# jan_ray.net
KiCad netlist of a schematic drawn in EAGLE
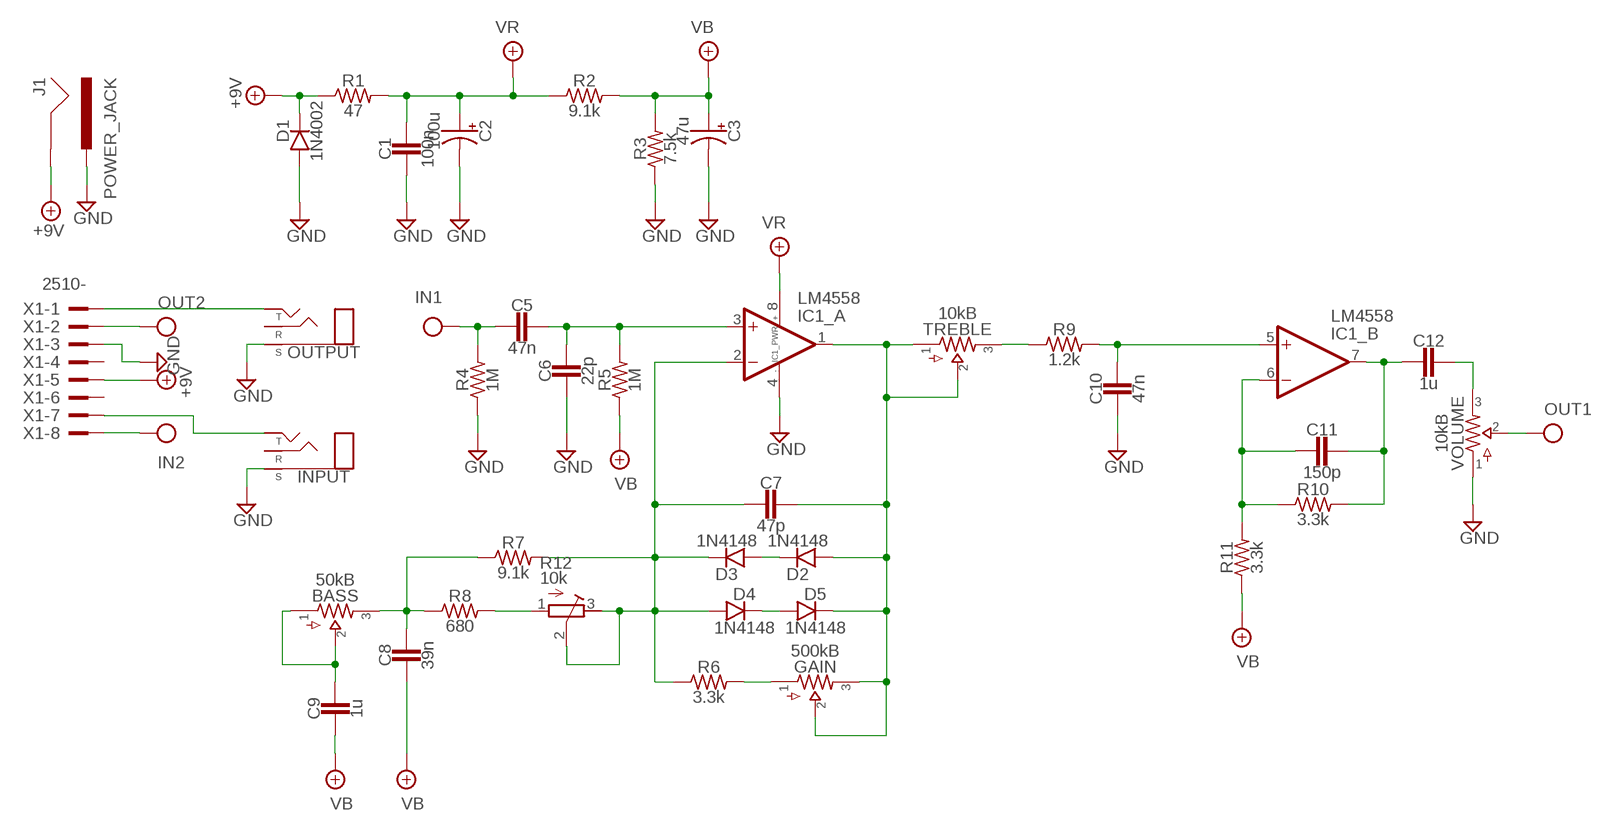
[diagram p0: schematic, sheet 1]

(export (version "E")
  (design (tool "Eeschema 10.0.6"))
  (components
    (comp (ref "BASS")
      (value "50kB")
      (footprint "eagle-import:16MM")
      (libsource (lib "eagle-import") (part "POTS16MM"))
    )
    (comp (ref "C1")
      (value "100n")
      (footprint "eagle-import:050X030_025_2")
      (libsource (lib "eagle-import") (part "CER/FILM2"))
    )
    (comp (ref "C2")
      (value "100u")
      (footprint "eagle-import:050_020")
      (libsource (lib "eagle-import") (part "0500"))
    )
    (comp (ref "C3")
      (value "47u")
      (footprint "eagle-import:050_020")
      (libsource (lib "eagle-import") (part "0500"))
    )
    (comp (ref "C5")
      (value "47n")
      (footprint "eagle-import:BOX_SMALL")
      (libsource (lib "eagle-import") (part "CER/FILMBOX.1"))
    )
    (comp (ref "C6")
      (value "22p")
      (footprint "eagle-import:050X030_025_2")
      (libsource (lib "eagle-import") (part "CER/FILM2"))
    )
    (comp (ref "C7")
      (value "47p")
      (footprint "eagle-import:050X030_025_2")
      (libsource (lib "eagle-import") (part "CER/FILM2"))
    )
    (comp (ref "C8")
      (value "39n")
      (footprint "eagle-import:BOX_SMALL")
      (libsource (lib "eagle-import") (part "CER/FILMBOX.1"))
    )
    (comp (ref "C9")
      (value "1u")
      (footprint "eagle-import:BOX_BIG")
      (libsource (lib "eagle-import") (part "CER/FILMBOX.3"))
    )
    (comp (ref "C10")
      (value "47n")
      (footprint "eagle-import:BOX_SMALL")
      (libsource (lib "eagle-import") (part "CER/FILMBOX.1"))
    )
    (comp (ref "C11")
      (value "150p")
      (footprint "eagle-import:050X030_025_2")
      (libsource (lib "eagle-import") (part "CER/FILM2"))
    )
    (comp (ref "C12")
      (value "1u")
      (footprint "eagle-import:BOX_BIG")
      (libsource (lib "eagle-import") (part "CER/FILMBOX.3"))
    )
    (comp (ref "D1")
      (value "1N4002")
      (footprint "eagle-import:DO41-2")
      (libsource (lib "eagle-import") (part "DO41.2"))
    )
    (comp (ref "D2")
      (value "1N4148")
      (footprint "eagle-import:DO35-2")
      (libsource (lib "eagle-import") (part "DO35.2"))
    )
    (comp (ref "D3")
      (value "1N4148")
      (footprint "eagle-import:DO35-2")
      (libsource (lib "eagle-import") (part "DO35.2"))
    )
    (comp (ref "D4")
      (value "1N4148")
      (footprint "eagle-import:DO35-2")
      (libsource (lib "eagle-import") (part "DO35.2"))
    )
    (comp (ref "D5")
      (value "1N4148")
      (footprint "eagle-import:DO35-2")
      (libsource (lib "eagle-import") (part "DO35.2"))
    )
    (comp (ref "GAIN")
      (value "500kB")
      (footprint "eagle-import:16MM")
      (libsource (lib "eagle-import") (part "POTS16MM"))
    )
    (comp (ref "IC1")
      (value "LM4558")
      (footprint "eagle-import:DIL08")
      (libsource (lib "eagle-import") (part "DUALTH"))
    )
    (comp (ref "INPUT")
      (value "STEREONMJ")
      (footprint "eagle-import:NMJ6HCD2")
      (libsource (lib "eagle-import") (part "STEREONMJ"))
    )
    (comp (ref "J1")
      (value "POWER_JACK")
      (footprint "eagle-import:POWER_JACK_PTH")
      (libsource (lib "eagle-import") (part "POWER_JACK"))
    )
    (comp (ref "OUTPUT")
      (value "STEREONMJ")
      (footprint "eagle-import:NMJ6HCD2")
      (libsource (lib "eagle-import") (part "STEREONMJ"))
    )
    (comp (ref "R1")
      (value "47")
      (footprint "eagle-import:R0207_3")
      (libsource (lib "eagle-import") (part "R_.3B"))
    )
    (comp (ref "R2")
      (value "9.1k")
      (footprint "eagle-import:R0207_3")
      (libsource (lib "eagle-import") (part "R_.3B"))
    )
    (comp (ref "R3")
      (value "7.5k")
      (footprint "eagle-import:R0207_3")
      (libsource (lib "eagle-import") (part "R_.3B"))
    )
    (comp (ref "R4")
      (value "1M")
      (footprint "eagle-import:R0207_3")
      (libsource (lib "eagle-import") (part "R_.3B"))
    )
    (comp (ref "R5")
      (value "1M")
      (footprint "eagle-import:R0207_3")
      (libsource (lib "eagle-import") (part "R_.3B"))
    )
    (comp (ref "R6")
      (value "3.3k")
      (footprint "eagle-import:R0207_3")
      (libsource (lib "eagle-import") (part "R_.3B"))
    )
    (comp (ref "R7")
      (value "9.1k")
      (footprint "eagle-import:R0207_3")
      (libsource (lib "eagle-import") (part "R_.3B"))
    )
    (comp (ref "R8")
      (value "680")
      (footprint "eagle-import:R0207_3")
      (libsource (lib "eagle-import") (part "R_.3B"))
    )
    (comp (ref "R9")
      (value "1.2k")
      (footprint "eagle-import:R0207_3")
      (libsource (lib "eagle-import") (part "R_.3B"))
    )
    (comp (ref "R10")
      (value "3.3k")
      (footprint "eagle-import:R0207_3")
      (libsource (lib "eagle-import") (part "R_.3B"))
    )
    (comp (ref "R11")
      (value "3.3k")
      (footprint "eagle-import:R0207_3")
      (libsource (lib "eagle-import") (part "R_.3B"))
    )
    (comp (ref "R12")
      (value "10k")
      (footprint "eagle-import:RTRIM3296W")
      (libsource (lib "eagle-import") (part "R-TRIMM3296W"))
    )
    (comp (ref "TREBLE")
      (value "10kB")
      (footprint "eagle-import:16MM")
      (libsource (lib "eagle-import") (part "POTS16MM"))
    )
    (comp (ref "VOLUME")
      (value "10kB")
      (footprint "eagle-import:16MM")
      (libsource (lib "eagle-import") (part "POTS16MM"))
    )
    (comp (ref "X1")
      (value "2510-")
      (footprint "eagle-import:PAK100_2500-10")
      (fields (field (name "MF") "3M") (field (name "MPN") "2510-6002UB"))
      (libsource (lib "eagle-import") (part "2510-"))
    )
  )
  (nets
    (net (code "1") (name "+9V") (class "Default")
      (node (ref "D1") (pin "C") (pinfunction "C_C") (pintype "passive"))
      (node (ref "J1") (pin "GND") (pinfunction "GND_GND") (pintype "bidirectional"))
      (node (ref "R1") (pin "1") (pinfunction "1_1") (pintype "passive"))
      (node (ref "X1") (pin "5") (pinfunction "KL_5") (pintype "passive"))
    )
    (net (code "2") (name "GND") (class "Default")
      (node (ref "C1") (pin "2") (pinfunction "2_2") (pintype "passive"))
      (node (ref "C10") (pin "2") (pinfunction "2_2") (pintype "passive"))
      (node (ref "C2") (pin "-") (pinfunction "-_-") (pintype "passive"))
      (node (ref "C3") (pin "-") (pinfunction "-_-") (pintype "passive"))
      (node (ref "C6") (pin "2") (pinfunction "2_2") (pintype "passive"))
      (node (ref "D1") (pin "A") (pinfunction "A_A") (pintype "passive"))
      (node (ref "IC1") (pin "4") (pinfunction "V-_4") (pintype "power_in"))
      (node (ref "INPUT") (pin "S") (pinfunction "S_S") (pintype "passive"))
      (node (ref "J1") (pin "PWR") (pinfunction "PWR_PWR") (pintype "bidirectional"))
      (node (ref "OUTPUT") (pin "S") (pinfunction "S_S") (pintype "passive"))
      (node (ref "R3") (pin "1") (pinfunction "1_1") (pintype "passive"))
      (node (ref "R4") (pin "1") (pinfunction "1_1") (pintype "passive"))
      (node (ref "VOLUME") (pin "1") (pinfunction "1_1") (pintype "passive"))
      (node (ref "X1") (pin "3") (pinfunction "KL_3") (pintype "passive"))
    )
    (net (code "3") (name "IN") (class "Default")
      (node (ref "C5") (pin "2") (pinfunction "2_2") (pintype "passive"))
      (node (ref "R4") (pin "2") (pinfunction "2_2") (pintype "passive"))
      (node (ref "X1") (pin "8") (pinfunction "KL_8") (pintype "passive"))
    )
    (net (code "4") (name "Net-(BASS-Pad1)") (class "Default")
      (node (ref "BASS") (pin "1") (pinfunction "1_1") (pintype "passive"))
      (node (ref "BASS") (pin "2") (pinfunction "2_2") (pintype "passive"))
      (node (ref "C9") (pin "1") (pinfunction "1_1") (pintype "passive"))
    )
    (net (code "5") (name "Net-(BASS-Pad3)") (class "Default")
      (node (ref "BASS") (pin "3") (pinfunction "3_3") (pintype "passive"))
      (node (ref "C8") (pin "1") (pinfunction "1_1") (pintype "passive"))
      (node (ref "R7") (pin "1") (pinfunction "1_1") (pintype "passive"))
      (node (ref "R8") (pin "1") (pinfunction "1_1") (pintype "passive"))
    )
    (net (code "6") (name "Net-(C12-Pad1)") (class "Default")
      (node (ref "C12") (pin "1") (pinfunction "1_1") (pintype "passive"))
      (node (ref "VOLUME") (pin "3") (pinfunction "3_3") (pintype "passive"))
    )
    (net (code "7") (name "Net-(D2-PadC)") (class "Default")
      (node (ref "D2") (pin "C") (pinfunction "C_C") (pintype "passive"))
      (node (ref "D3") (pin "A") (pinfunction "A_A") (pintype "passive"))
    )
    (net (code "8") (name "Net-(D4-PadC)") (class "Default")
      (node (ref "D4") (pin "C") (pinfunction "C_C") (pintype "passive"))
      (node (ref "D5") (pin "A") (pinfunction "A_A") (pintype "passive"))
    )
    (net (code "9") (name "Net-(GAIN-Pad1)") (class "Default")
      (node (ref "GAIN") (pin "1") (pinfunction "1_1") (pintype "passive"))
      (node (ref "R6") (pin "2") (pinfunction "2_2") (pintype "passive"))
    )
    (net (code "10") (name "Net-(IC1A-+IN)") (class "Default")
      (node (ref "C5") (pin "1") (pinfunction "1_1") (pintype "passive"))
      (node (ref "C6") (pin "1") (pinfunction "1_1") (pintype "passive"))
      (node (ref "IC1") (pin "3") (pinfunction "+IN_3") (pintype "input"))
      (node (ref "R5") (pin "2") (pinfunction "2_2") (pintype "passive"))
    )
    (net (code "11") (name "Net-(IC1A--IN)") (class "Default")
      (node (ref "C7") (pin "2") (pinfunction "2_2") (pintype "passive"))
      (node (ref "D3") (pin "C") (pinfunction "C_C") (pintype "passive"))
      (node (ref "D4") (pin "A") (pinfunction "A_A") (pintype "passive"))
      (node (ref "IC1") (pin "2") (pinfunction "-IN_2") (pintype "input"))
      (node (ref "R12") (pin "2") (pinfunction "S_2") (pintype "passive"))
      (node (ref "R12") (pin "3") (pinfunction "E_3") (pintype "passive"))
      (node (ref "R6") (pin "1") (pinfunction "1_1") (pintype "passive"))
      (node (ref "R7") (pin "2") (pinfunction "2_2") (pintype "passive"))
    )
    (net (code "12") (name "Net-(IC1A-OUT)") (class "Default")
      (node (ref "C7") (pin "1") (pinfunction "1_1") (pintype "passive"))
      (node (ref "D2") (pin "A") (pinfunction "A_A") (pintype "passive"))
      (node (ref "D5") (pin "C") (pinfunction "C_C") (pintype "passive"))
      (node (ref "GAIN") (pin "2") (pinfunction "2_2") (pintype "passive"))
      (node (ref "GAIN") (pin "3") (pinfunction "3_3") (pintype "passive"))
      (node (ref "IC1") (pin "1") (pinfunction "OUT_1") (pintype "output"))
      (node (ref "TREBLE") (pin "1") (pinfunction "1_1") (pintype "passive"))
      (node (ref "TREBLE") (pin "2") (pinfunction "2_2") (pintype "passive"))
    )
    (net (code "13") (name "Net-(IC1B-+IN)") (class "Default")
      (node (ref "C10") (pin "1") (pinfunction "1_1") (pintype "passive"))
      (node (ref "IC1") (pin "5") (pinfunction "+IN_5") (pintype "input"))
      (node (ref "R9") (pin "2") (pinfunction "2_2") (pintype "passive"))
    )
    (net (code "14") (name "Net-(IC1B--IN)") (class "Default")
      (node (ref "C11") (pin "2") (pinfunction "2_2") (pintype "passive"))
      (node (ref "IC1") (pin "6") (pinfunction "-IN_6") (pintype "input"))
      (node (ref "R10") (pin "1") (pinfunction "1_1") (pintype "passive"))
      (node (ref "R11") (pin "2") (pinfunction "2_2") (pintype "passive"))
    )
    (net (code "15") (name "Net-(IC1B-OUT)") (class "Default")
      (node (ref "C11") (pin "1") (pinfunction "1_1") (pintype "passive"))
      (node (ref "C12") (pin "2") (pinfunction "2_2") (pintype "passive"))
      (node (ref "IC1") (pin "7") (pinfunction "OUT_7") (pintype "output"))
      (node (ref "R10") (pin "2") (pinfunction "2_2") (pintype "passive"))
    )
    (net (code "16") (name "Net-(R9-Pad1)") (class "Default")
      (node (ref "R9") (pin "1") (pinfunction "1_1") (pintype "passive"))
      (node (ref "TREBLE") (pin "3") (pinfunction "3_3") (pintype "passive"))
    )
    (net (code "17") (name "Net-(R12-A)") (class "Default")
      (node (ref "R12") (pin "1") (pinfunction "A_1") (pintype "passive"))
      (node (ref "R8") (pin "2") (pinfunction "2_2") (pintype "passive"))
    )
    (net (code "18") (name "Net-(X1A-KL)") (class "Default")
      (node (ref "OUTPUT") (pin "T") (pinfunction "T_T") (pintype "passive"))
      (node (ref "X1") (pin "1") (pinfunction "KL_1") (pintype "passive"))
    )
    (net (code "19") (name "Net-(X1G-KL)") (class "Default")
      (node (ref "INPUT") (pin "T") (pinfunction "T_T") (pintype "passive"))
      (node (ref "X1") (pin "7") (pinfunction "KL_7") (pintype "passive"))
    )
    (net (code "20") (name "OUT") (class "Default")
      (node (ref "VOLUME") (pin "2") (pinfunction "2_2") (pintype "passive"))
      (node (ref "X1") (pin "2") (pinfunction "KL_2") (pintype "passive"))
    )
    (net (code "21") (name "VB") (class "Default")
      (node (ref "C3") (pin "+") (pinfunction "+_+") (pintype "passive"))
      (node (ref "C8") (pin "2") (pinfunction "2_2") (pintype "passive"))
      (node (ref "C9") (pin "2") (pinfunction "2_2") (pintype "passive"))
      (node (ref "R11") (pin "1") (pinfunction "1_1") (pintype "passive"))
      (node (ref "R2") (pin "2") (pinfunction "2_2") (pintype "passive"))
      (node (ref "R3") (pin "2") (pinfunction "2_2") (pintype "passive"))
      (node (ref "R5") (pin "1") (pinfunction "1_1") (pintype "passive"))
    )
    (net (code "22") (name "VR") (class "Default")
      (node (ref "C1") (pin "1") (pinfunction "1_1") (pintype "passive"))
      (node (ref "C2") (pin "+") (pinfunction "+_+") (pintype "passive"))
      (node (ref "IC1") (pin "8") (pinfunction "V+_8") (pintype "power_in"))
      (node (ref "R1") (pin "2") (pinfunction "2_2") (pintype "passive"))
      (node (ref "R2") (pin "1") (pinfunction "1_1") (pintype "passive"))
    )
    (net (code "23") (name "unconnected-(INPUT-PadR)") (class "Default")
      (node (ref "INPUT") (pin "R") (pinfunction "R_R") (pintype "passive"))
    )
    (net (code "24") (name "unconnected-(OUTPUT-PadR)") (class "Default")
      (node (ref "OUTPUT") (pin "R") (pinfunction "R_R") (pintype "passive"))
    )
    (net (code "25") (name "unconnected-(X1D-KL-Pad4)") (class "Default")
      (node (ref "X1") (pin "4") (pinfunction "KL_4") (pintype "passive"))
    )
    (net (code "26") (name "unconnected-(X1F-KL-Pad6)") (class "Default")
      (node (ref "X1") (pin "6") (pinfunction "KL_6") (pintype "passive"))
    )
  )
)
